# caliper.net
KiCad netlist of a schematic drawn in EAGLE
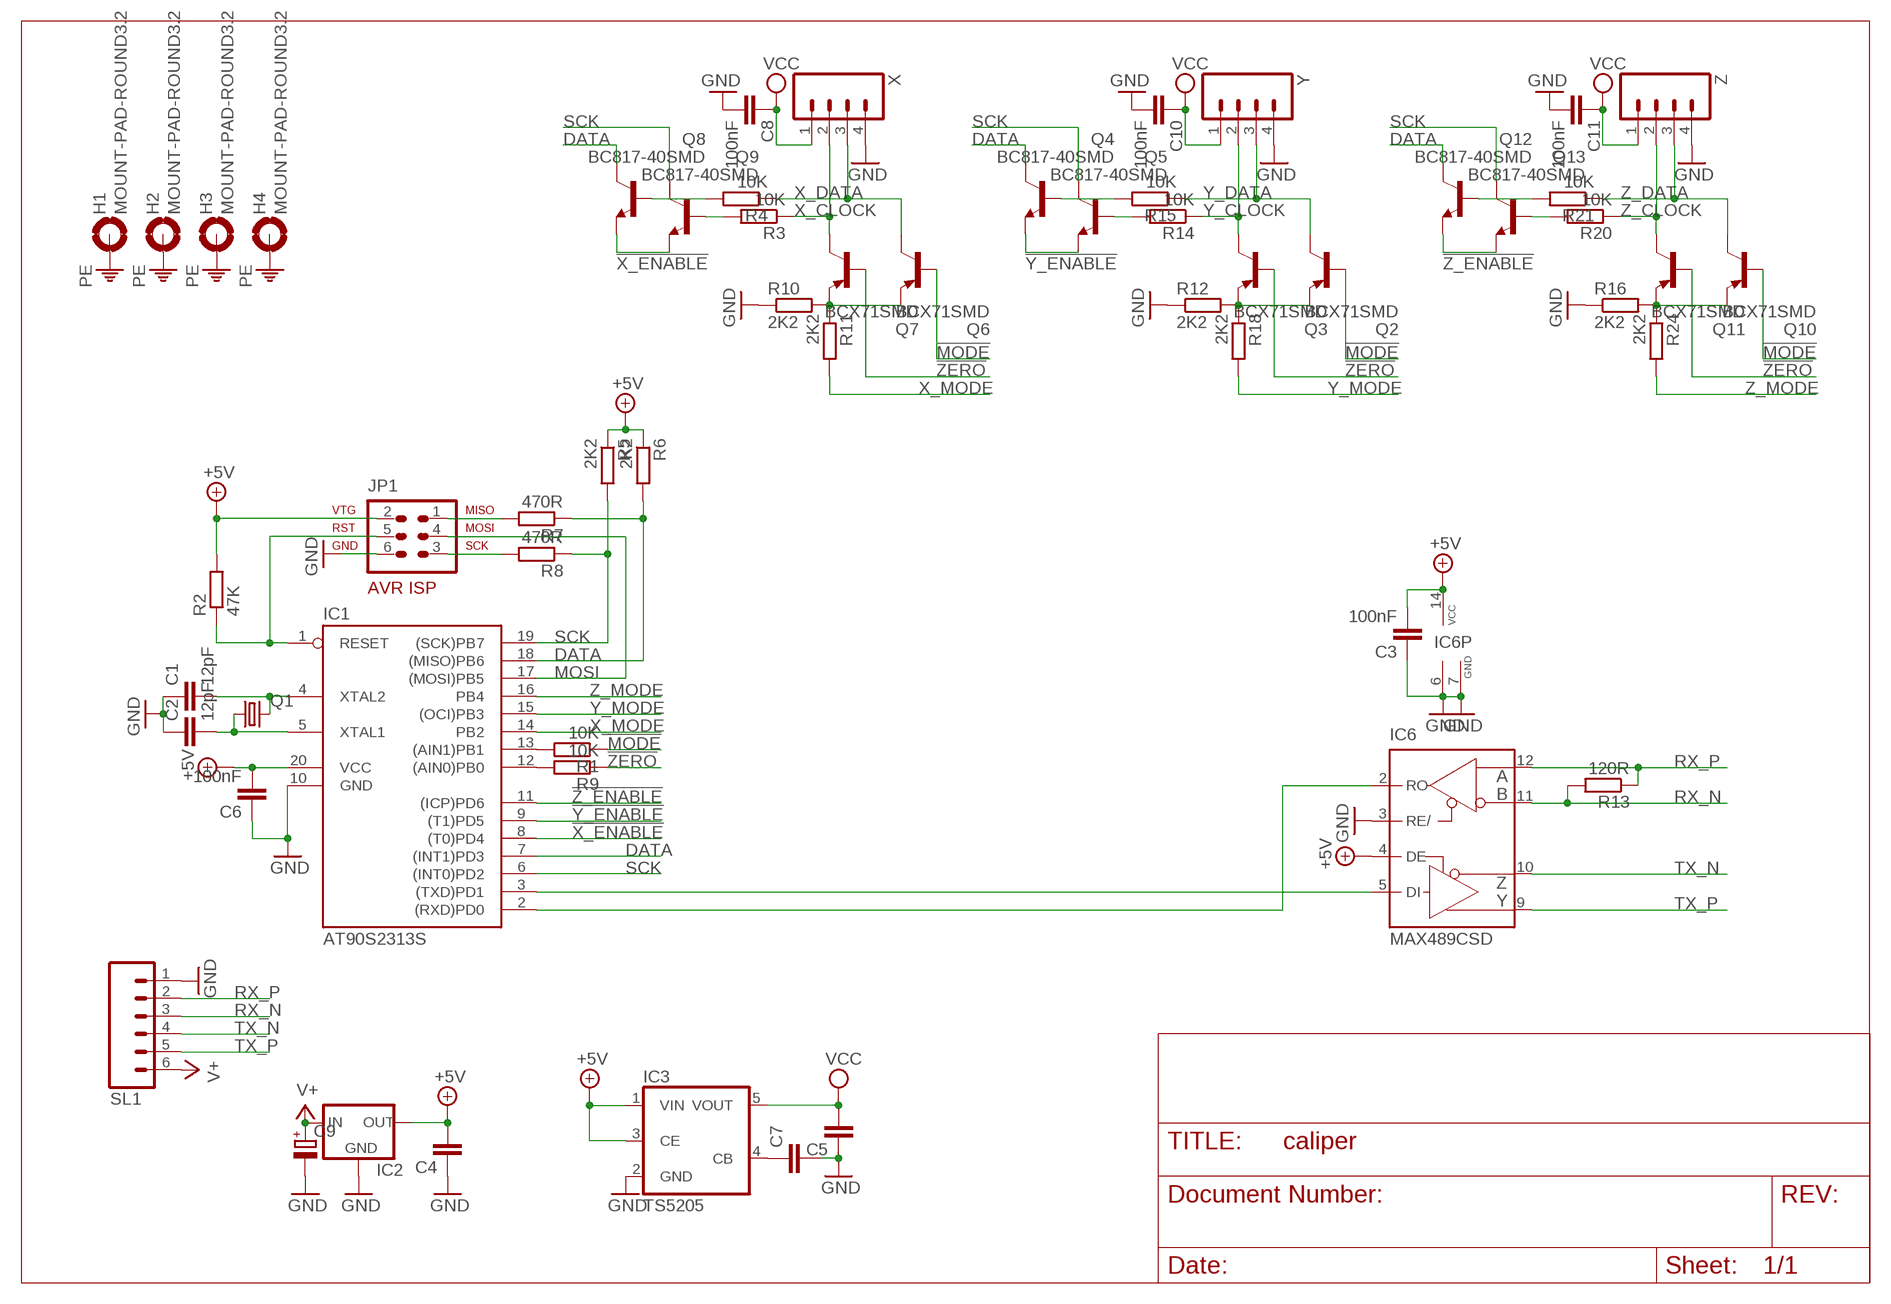
[diagram p0: schematic, sheet 1]

(export (version "E")
  (design (tool "Eeschema 10.0.6"))
  (components
    (comp (ref "C1")
      (value "12pF")
      (footprint "eagle-import:C0805")
      (libsource (lib "eagle-import") (part "C-EUC0805"))
    )
    (comp (ref "C2")
      (value "12pF")
      (footprint "eagle-import:C0805")
      (libsource (lib "eagle-import") (part "C-EUC0805"))
    )
    (comp (ref "C3")
      (value "100nF")
      (footprint "eagle-import:C0805")
      (libsource (lib "eagle-import") (part "C-EUC0805"))
    )
    (comp (ref "C4")
      (value "C-EUC0805")
      (footprint "eagle-import:C0805")
      (libsource (lib "eagle-import") (part "C-EUC0805"))
    )
    (comp (ref "C5")
      (value "C-EUC0805")
      (footprint "eagle-import:C0805")
      (libsource (lib "eagle-import") (part "C-EUC0805"))
    )
    (comp (ref "C6")
      (value "100nF")
      (footprint "eagle-import:C0805")
      (libsource (lib "eagle-import") (part "C-EUC0805"))
    )
    (comp (ref "C7")
      (value "C-EUC0805")
      (footprint "eagle-import:C0805")
      (libsource (lib "eagle-import") (part "C-EUC0805"))
    )
    (comp (ref "C8")
      (value "100nF")
      (footprint "eagle-import:C0805")
      (libsource (lib "eagle-import") (part "C-EUC0805"))
    )
    (comp (ref "C9")
      (value "CPOL-EUE3.5-8")
      (footprint "eagle-import:E3,5-8")
      (libsource (lib "eagle-import") (part "CPOL-EUE3.5-8"))
    )
    (comp (ref "C10")
      (value "100nF")
      (footprint "eagle-import:C0805")
      (libsource (lib "eagle-import") (part "C-EUC0805"))
    )
    (comp (ref "C11")
      (value "100nF")
      (footprint "eagle-import:C0805")
      (libsource (lib "eagle-import") (part "C-EUC0805"))
    )
    (comp (ref "H1")
      (value "MOUNT-PAD-ROUND3.2")
      (footprint "eagle-import:3,2-PAD")
      (libsource (lib "eagle-import") (part "MOUNT-PAD-ROUND3.2"))
    )
    (comp (ref "H2")
      (value "MOUNT-PAD-ROUND3.2")
      (footprint "eagle-import:3,2-PAD")
      (libsource (lib "eagle-import") (part "MOUNT-PAD-ROUND3.2"))
    )
    (comp (ref "H3")
      (value "MOUNT-PAD-ROUND3.2")
      (footprint "eagle-import:3,2-PAD")
      (libsource (lib "eagle-import") (part "MOUNT-PAD-ROUND3.2"))
    )
    (comp (ref "H4")
      (value "MOUNT-PAD-ROUND3.2")
      (footprint "eagle-import:3,2-PAD")
      (libsource (lib "eagle-import") (part "MOUNT-PAD-ROUND3.2"))
    )
    (comp (ref "IC1")
      (value "AT90S2313S")
      (footprint "eagle-import:SO20L")
      (libsource (lib "eagle-import") (part "AT90S2313S"))
    )
    (comp (ref "IC2")
      (value "78XXS")
      (footprint "eagle-import:78XXS")
      (libsource (lib "eagle-import") (part "78XXS"))
    )
    (comp (ref "IC3")
      (value "TS5205")
      (footprint "eagle-import:SOT25")
      (libsource (lib "eagle-import") (part "TS5205"))
    )
    (comp (ref "IC6")
      (value "MAX489CSD")
      (footprint "eagle-import:SO14")
      (libsource (lib "eagle-import") (part "MAX489CSD"))
    )
    (comp (ref "JP1")
      (value "AVR-ISP-6")
      (footprint "eagle-import:AVR-ISP-6")
      (libsource (lib "eagle-import") (part "AVR-ISP-6"))
    )
    (comp (ref "Q1")
      (value "CRYTALHC49S")
      (footprint "eagle-import:HC49_S")
      (libsource (lib "eagle-import") (part "CRYTALHC49S"))
    )
    (comp (ref "Q2")
      (value "BCX71SMD")
      (footprint "eagle-import:SOT23")
      (libsource (lib "eagle-import") (part "BCX71SMD"))
    )
    (comp (ref "Q3")
      (value "BCX71SMD")
      (footprint "eagle-import:SOT23")
      (libsource (lib "eagle-import") (part "BCX71SMD"))
    )
    (comp (ref "Q4")
      (value "BC817-40SMD")
      (footprint "eagle-import:SOT23-BEC")
      (libsource (lib "eagle-import") (part "BC817SMD-40"))
    )
    (comp (ref "Q5")
      (value "BC817-40SMD")
      (footprint "eagle-import:SOT23-BEC")
      (libsource (lib "eagle-import") (part "BC817SMD-40"))
    )
    (comp (ref "Q6")
      (value "BCX71SMD")
      (footprint "eagle-import:SOT23")
      (libsource (lib "eagle-import") (part "BCX71SMD"))
    )
    (comp (ref "Q7")
      (value "BCX71SMD")
      (footprint "eagle-import:SOT23")
      (libsource (lib "eagle-import") (part "BCX71SMD"))
    )
    (comp (ref "Q8")
      (value "BC817-40SMD")
      (footprint "eagle-import:SOT23-BEC")
      (libsource (lib "eagle-import") (part "BC817SMD-40"))
    )
    (comp (ref "Q9")
      (value "BC817-40SMD")
      (footprint "eagle-import:SOT23-BEC")
      (libsource (lib "eagle-import") (part "BC817SMD-40"))
    )
    (comp (ref "Q10")
      (value "BCX71SMD")
      (footprint "eagle-import:SOT23")
      (libsource (lib "eagle-import") (part "BCX71SMD"))
    )
    (comp (ref "Q11")
      (value "BCX71SMD")
      (footprint "eagle-import:SOT23")
      (libsource (lib "eagle-import") (part "BCX71SMD"))
    )
    (comp (ref "Q12")
      (value "BC817-40SMD")
      (footprint "eagle-import:SOT23-BEC")
      (libsource (lib "eagle-import") (part "BC817SMD-40"))
    )
    (comp (ref "Q13")
      (value "BC817-40SMD")
      (footprint "eagle-import:SOT23-BEC")
      (libsource (lib "eagle-import") (part "BC817SMD-40"))
    )
    (comp (ref "R1")
      (value "10K")
      (footprint "eagle-import:R0805")
      (libsource (lib "eagle-import") (part "R-EU_R0805"))
    )
    (comp (ref "R2")
      (value "47K")
      (footprint "eagle-import:R0805")
      (libsource (lib "eagle-import") (part "R-EU_R0805"))
    )
    (comp (ref "R3")
      (value "10K")
      (footprint "eagle-import:R0805")
      (libsource (lib "eagle-import") (part "R-EU_R0805"))
    )
    (comp (ref "R4")
      (value "10K")
      (footprint "eagle-import:R0805")
      (libsource (lib "eagle-import") (part "R-EU_R0805"))
    )
    (comp (ref "R5")
      (value "2K2")
      (footprint "eagle-import:R0805")
      (libsource (lib "eagle-import") (part "R-EU_R0805"))
    )
    (comp (ref "R6")
      (value "2K2")
      (footprint "eagle-import:R0805")
      (libsource (lib "eagle-import") (part "R-EU_R0805"))
    )
    (comp (ref "R7")
      (value "470R")
      (footprint "eagle-import:R0805")
      (libsource (lib "eagle-import") (part "R-EU_R0805"))
    )
    (comp (ref "R8")
      (value "470R")
      (footprint "eagle-import:R0805")
      (libsource (lib "eagle-import") (part "R-EU_R0805"))
    )
    (comp (ref "R9")
      (value "10K")
      (footprint "eagle-import:R0805")
      (libsource (lib "eagle-import") (part "R-EU_R0805"))
    )
    (comp (ref "R10")
      (value "2K2")
      (footprint "eagle-import:R0805")
      (libsource (lib "eagle-import") (part "R-EU_R0805"))
    )
    (comp (ref "R11")
      (value "2K2")
      (footprint "eagle-import:R0805")
      (libsource (lib "eagle-import") (part "R-EU_R0805"))
    )
    (comp (ref "R12")
      (value "2K2")
      (footprint "eagle-import:R0805")
      (libsource (lib "eagle-import") (part "R-EU_R0805"))
    )
    (comp (ref "R13")
      (value "120R")
      (footprint "eagle-import:R0805")
      (libsource (lib "eagle-import") (part "R-EU_R0805"))
    )
    (comp (ref "R14")
      (value "10K")
      (footprint "eagle-import:R0805")
      (libsource (lib "eagle-import") (part "R-EU_R0805"))
    )
    (comp (ref "R15")
      (value "10K")
      (footprint "eagle-import:R0805")
      (libsource (lib "eagle-import") (part "R-EU_R0805"))
    )
    (comp (ref "R16")
      (value "2K2")
      (footprint "eagle-import:R0805")
      (libsource (lib "eagle-import") (part "R-EU_R0805"))
    )
    (comp (ref "R18")
      (value "2K2")
      (footprint "eagle-import:R0805")
      (libsource (lib "eagle-import") (part "R-EU_R0805"))
    )
    (comp (ref "R20")
      (value "10K")
      (footprint "eagle-import:R0805")
      (libsource (lib "eagle-import") (part "R-EU_R0805"))
    )
    (comp (ref "R21")
      (value "10K")
      (footprint "eagle-import:R0805")
      (libsource (lib "eagle-import") (part "R-EU_R0805"))
    )
    (comp (ref "R24")
      (value "2K2")
      (footprint "eagle-import:R0805")
      (libsource (lib "eagle-import") (part "R-EU_R0805"))
    )
    (comp (ref "SL1")
      (value "M06")
      (footprint "eagle-import:06P")
      (libsource (lib "eagle-import") (part "M06"))
    )
    (comp (ref "X")
      (value "M04")
      (footprint "eagle-import:04P")
      (libsource (lib "eagle-import") (part "M04"))
    )
    (comp (ref "Y")
      (value "M04")
      (footprint "eagle-import:04P")
      (libsource (lib "eagle-import") (part "M04"))
    )
    (comp (ref "Z")
      (value "M04")
      (footprint "eagle-import:04P")
      (libsource (lib "eagle-import") (part "M04"))
    )
  )
  (nets
    (net (code "1") (name "+5V") (class "Default")
      (node (ref "C3") (pin "2") (pinfunction "2_2") (pintype "passive"))
      (node (ref "C4") (pin "2") (pinfunction "2_2") (pintype "passive"))
      (node (ref "C6") (pin "2") (pinfunction "2_2") (pintype "passive"))
      (node (ref "IC1") (pin "20") (pinfunction "VCC_20") (pintype "power_in"))
      (node (ref "IC2") (pin "OUT") (pinfunction "OUT_OUT") (pintype "passive"))
      (node (ref "IC3") (pin "1") (pinfunction "VIN_1") (pintype "input"))
      (node (ref "IC3") (pin "3") (pinfunction "CE_3") (pintype "input"))
      (node (ref "IC6") (pin "14") (pinfunction "VCC_14") (pintype "power_in"))
      (node (ref "IC6") (pin "4") (pinfunction "DE_4") (pintype "input"))
      (node (ref "JP1") (pin "2") (pinfunction "2_2") (pintype "passive"))
      (node (ref "R2") (pin "2") (pinfunction "2_2") (pintype "passive"))
      (node (ref "R5") (pin "1") (pinfunction "1_1") (pintype "passive"))
      (node (ref "R6") (pin "1") (pinfunction "1_1") (pintype "passive"))
    )
    (net (code "2") (name "/DATA") (class "Default")
      (node (ref "IC1") (pin "18") (pinfunction "(MISO)PB6_18") (pintype "bidirectional"))
      (node (ref "IC1") (pin "7") (pinfunction "(INT1)PD3_7") (pintype "bidirectional"))
      (node (ref "Q12") (pin "C") (pinfunction "C_C") (pintype "passive"))
      (node (ref "Q4") (pin "C") (pinfunction "C_C") (pintype "passive"))
      (node (ref "Q8") (pin "C") (pinfunction "C_C") (pintype "passive"))
      (node (ref "R6") (pin "2") (pinfunction "2_2") (pintype "passive"))
      (node (ref "R7") (pin "1") (pinfunction "1_1") (pintype "passive"))
    )
    (net (code "3") (name "/MOSI") (class "Default")
      (node (ref "IC1") (pin "17") (pinfunction "(MOSI)PB5_17") (pintype "bidirectional"))
      (node (ref "JP1") (pin "4") (pinfunction "4_4") (pintype "passive"))
    )
    (net (code "4") (name "/RX_N") (class "Default")
      (node (ref "IC6") (pin "11") (pinfunction "B_11") (pintype "passive"))
      (node (ref "R13") (pin "2") (pinfunction "2_2") (pintype "passive"))
      (node (ref "SL1") (pin "3") (pinfunction "3_3") (pintype "passive"))
    )
    (net (code "5") (name "/RX_P") (class "Default")
      (node (ref "IC6") (pin "12") (pinfunction "A_12") (pintype "passive"))
      (node (ref "R13") (pin "1") (pinfunction "1_1") (pintype "passive"))
      (node (ref "SL1") (pin "2") (pinfunction "2_2") (pintype "passive"))
    )
    (net (code "6") (name "/SCK") (class "Default")
      (node (ref "IC1") (pin "19") (pinfunction "(SCK)PB7_19") (pintype "bidirectional"))
      (node (ref "IC1") (pin "6") (pinfunction "(INT0)PD2_6") (pintype "bidirectional"))
      (node (ref "Q13") (pin "C") (pinfunction "C_C") (pintype "passive"))
      (node (ref "Q5") (pin "C") (pinfunction "C_C") (pintype "passive"))
      (node (ref "Q9") (pin "C") (pinfunction "C_C") (pintype "passive"))
      (node (ref "R5") (pin "2") (pinfunction "2_2") (pintype "passive"))
      (node (ref "R8") (pin "1") (pinfunction "1_1") (pintype "passive"))
    )
    (net (code "7") (name "/TX_N") (class "Default")
      (node (ref "IC6") (pin "10") (pinfunction "Z_10") (pintype "passive"))
      (node (ref "SL1") (pin "4") (pinfunction "4_4") (pintype "passive"))
    )
    (net (code "8") (name "/TX_P") (class "Default")
      (node (ref "IC6") (pin "9") (pinfunction "Y_9") (pintype "passive"))
      (node (ref "SL1") (pin "5") (pinfunction "5_5") (pintype "passive"))
    )
    (net (code "9") (name "/X_CLOCK") (class "Default")
      (node (ref "Q7") (pin "3") (pinfunction "C_3") (pintype "passive"))
      (node (ref "R3") (pin "1") (pinfunction "1_1") (pintype "passive"))
      (node (ref "X") (pin "2") (pinfunction "2_2") (pintype "passive"))
    )
    (net (code "10") (name "/X_DATA") (class "Default")
      (node (ref "Q6") (pin "3") (pinfunction "C_3") (pintype "passive"))
      (node (ref "R4") (pin "1") (pinfunction "1_1") (pintype "passive"))
      (node (ref "X") (pin "3") (pinfunction "3_3") (pintype "passive"))
    )
    (net (code "11") (name "/X_MODE") (class "Default")
      (node (ref "IC1") (pin "14") (pinfunction "PB2_14") (pintype "bidirectional"))
      (node (ref "R11") (pin "2") (pinfunction "2_2") (pintype "passive"))
    )
    (net (code "12") (name "/Y_CLOCK") (class "Default")
      (node (ref "Q3") (pin "3") (pinfunction "C_3") (pintype "passive"))
      (node (ref "R14") (pin "1") (pinfunction "1_1") (pintype "passive"))
      (node (ref "Y") (pin "2") (pinfunction "2_2") (pintype "passive"))
    )
    (net (code "13") (name "/Y_DATA") (class "Default")
      (node (ref "Q2") (pin "3") (pinfunction "C_3") (pintype "passive"))
      (node (ref "R15") (pin "1") (pinfunction "1_1") (pintype "passive"))
      (node (ref "Y") (pin "3") (pinfunction "3_3") (pintype "passive"))
    )
    (net (code "14") (name "/Y_MODE") (class "Default")
      (node (ref "IC1") (pin "15") (pinfunction "(OCI)PB3_15") (pintype "bidirectional"))
      (node (ref "R18") (pin "2") (pinfunction "2_2") (pintype "passive"))
    )
    (net (code "15") (name "/Z_CLOCK") (class "Default")
      (node (ref "Q11") (pin "3") (pinfunction "C_3") (pintype "passive"))
      (node (ref "R20") (pin "1") (pinfunction "1_1") (pintype "passive"))
      (node (ref "Z") (pin "2") (pinfunction "2_2") (pintype "passive"))
    )
    (net (code "16") (name "/Z_DATA") (class "Default")
      (node (ref "Q10") (pin "3") (pinfunction "C_3") (pintype "passive"))
      (node (ref "R21") (pin "1") (pinfunction "1_1") (pintype "passive"))
      (node (ref "Z") (pin "3") (pinfunction "3_3") (pintype "passive"))
    )
    (net (code "17") (name "/Z_MODE") (class "Default")
      (node (ref "IC1") (pin "16") (pinfunction "PB4_16") (pintype "bidirectional"))
      (node (ref "R24") (pin "2") (pinfunction "2_2") (pintype "passive"))
    )
    (net (code "18") (name "/~{MODE}") (class "Default")
      (node (ref "Q10") (pin "1") (pinfunction "B_1") (pintype "passive"))
      (node (ref "Q2") (pin "1") (pinfunction "B_1") (pintype "passive"))
      (node (ref "Q6") (pin "1") (pinfunction "B_1") (pintype "passive"))
      (node (ref "R1") (pin "1") (pinfunction "1_1") (pintype "passive"))
    )
    (net (code "19") (name "/~{X_ENABLE}") (class "Default")
      (node (ref "IC1") (pin "8") (pinfunction "(T0)PD4_8") (pintype "bidirectional"))
      (node (ref "Q8") (pin "E") (pinfunction "E_E") (pintype "passive"))
      (node (ref "Q9") (pin "E") (pinfunction "E_E") (pintype "passive"))
    )
    (net (code "20") (name "/~{Y_ENABLE}") (class "Default")
      (node (ref "IC1") (pin "9") (pinfunction "(T1)PD5_9") (pintype "bidirectional"))
      (node (ref "Q4") (pin "E") (pinfunction "E_E") (pintype "passive"))
      (node (ref "Q5") (pin "E") (pinfunction "E_E") (pintype "passive"))
    )
    (net (code "21") (name "/~{ZERO}") (class "Default")
      (node (ref "Q11") (pin "1") (pinfunction "B_1") (pintype "passive"))
      (node (ref "Q3") (pin "1") (pinfunction "B_1") (pintype "passive"))
      (node (ref "Q7") (pin "1") (pinfunction "B_1") (pintype "passive"))
      (node (ref "R9") (pin "1") (pinfunction "1_1") (pintype "passive"))
    )
    (net (code "22") (name "/~{Z_ENABLE}") (class "Default")
      (node (ref "IC1") (pin "11") (pinfunction "(ICP)PD6_11") (pintype "bidirectional"))
      (node (ref "Q12") (pin "E") (pinfunction "E_E") (pintype "passive"))
      (node (ref "Q13") (pin "E") (pinfunction "E_E") (pintype "passive"))
    )
    (net (code "23") (name "GND") (class "Default")
      (node (ref "C1") (pin "1") (pinfunction "1_1") (pintype "passive"))
      (node (ref "C10") (pin "2") (pinfunction "2_2") (pintype "passive"))
      (node (ref "C11") (pin "2") (pinfunction "2_2") (pintype "passive"))
      (node (ref "C2") (pin "1") (pinfunction "1_1") (pintype "passive"))
      (node (ref "C3") (pin "1") (pinfunction "1_1") (pintype "passive"))
      (node (ref "C4") (pin "1") (pinfunction "1_1") (pintype "passive"))
      (node (ref "C5") (pin "1") (pinfunction "1_1") (pintype "passive"))
      (node (ref "C6") (pin "1") (pinfunction "1_1") (pintype "passive"))
      (node (ref "C7") (pin "2") (pinfunction "2_2") (pintype "passive"))
      (node (ref "C8") (pin "2") (pinfunction "2_2") (pintype "passive"))
      (node (ref "C9") (pin "-") (pinfunction "-_-") (pintype "passive"))
      (node (ref "IC1") (pin "10") (pinfunction "GND_10") (pintype "power_in"))
      (node (ref "IC2") (pin "GND") (pinfunction "GND_GND") (pintype "input"))
      (node (ref "IC3") (pin "2") (pinfunction "GND_2") (pintype "passive"))
      (node (ref "IC6") (pin "3") (pinfunction "RE/_3") (pintype "input"))
      (node (ref "IC6") (pin "6") (pinfunction "GND_6") (pintype "power_in"))
      (node (ref "IC6") (pin "7") (pinfunction "GND_7") (pintype "power_in"))
      (node (ref "JP1") (pin "6") (pinfunction "6_6") (pintype "passive"))
      (node (ref "R10") (pin "1") (pinfunction "1_1") (pintype "passive"))
      (node (ref "R12") (pin "1") (pinfunction "1_1") (pintype "passive"))
      (node (ref "R16") (pin "1") (pinfunction "1_1") (pintype "passive"))
      (node (ref "SL1") (pin "1") (pinfunction "1_1") (pintype "passive"))
      (node (ref "X") (pin "4") (pinfunction "4_4") (pintype "passive"))
      (node (ref "Y") (pin "4") (pinfunction "4_4") (pintype "passive"))
      (node (ref "Z") (pin "4") (pinfunction "4_4") (pintype "passive"))
    )
    (net (code "24") (name "Net-(IC1-(AIN0)PB0)") (class "Default")
      (node (ref "IC1") (pin "12") (pinfunction "(AIN0)PB0_12") (pintype "bidirectional"))
      (node (ref "R9") (pin "2") (pinfunction "2_2") (pintype "passive"))
    )
    (net (code "25") (name "Net-(IC1-(AIN1)PB1)") (class "Default")
      (node (ref "IC1") (pin "13") (pinfunction "(AIN1)PB1_13") (pintype "bidirectional"))
      (node (ref "R1") (pin "2") (pinfunction "2_2") (pintype "passive"))
    )
    (net (code "26") (name "Net-(IC1-(RXD)PD0)") (class "Default")
      (node (ref "IC1") (pin "2") (pinfunction "(RXD)PD0_2") (pintype "bidirectional"))
      (node (ref "IC6") (pin "2") (pinfunction "RO_2") (pintype "output"))
    )
    (net (code "27") (name "Net-(IC1-(TXD)PD1)") (class "Default")
      (node (ref "IC1") (pin "3") (pinfunction "(TXD)PD1_3") (pintype "bidirectional"))
      (node (ref "IC6") (pin "5") (pinfunction "DI_5") (pintype "input"))
    )
    (net (code "28") (name "Net-(IC1-RESET)") (class "Default")
      (node (ref "IC1") (pin "1") (pinfunction "RESET_1") (pintype "bidirectional"))
      (node (ref "JP1") (pin "5") (pinfunction "5_5") (pintype "passive"))
      (node (ref "R2") (pin "1") (pinfunction "1_1") (pintype "passive"))
    )
    (net (code "29") (name "Net-(IC1-XTAL1)") (class "Default")
      (node (ref "C2") (pin "2") (pinfunction "2_2") (pintype "passive"))
      (node (ref "IC1") (pin "5") (pinfunction "XTAL1_5") (pintype "bidirectional"))
      (node (ref "Q1") (pin "1") (pinfunction "1_1") (pintype "passive"))
    )
    (net (code "30") (name "Net-(IC1-XTAL2)") (class "Default")
      (node (ref "C1") (pin "2") (pinfunction "2_2") (pintype "passive"))
      (node (ref "IC1") (pin "4") (pinfunction "XTAL2_4") (pintype "bidirectional"))
      (node (ref "Q1") (pin "2") (pinfunction "2_2") (pintype "passive"))
    )
    (net (code "31") (name "Net-(IC3-CB)") (class "Default")
      (node (ref "C7") (pin "1") (pinfunction "1_1") (pintype "passive"))
      (node (ref "IC3") (pin "4") (pinfunction "CB_4") (pintype "input"))
    )
    (net (code "32") (name "Net-(JP1-Pad1)") (class "Default")
      (node (ref "JP1") (pin "1") (pinfunction "1_1") (pintype "passive"))
      (node (ref "R7") (pin "2") (pinfunction "2_2") (pintype "passive"))
    )
    (net (code "33") (name "Net-(JP1-Pad3)") (class "Default")
      (node (ref "JP1") (pin "3") (pinfunction "3_3") (pintype "passive"))
      (node (ref "R8") (pin "2") (pinfunction "2_2") (pintype "passive"))
    )
    (net (code "34") (name "Net-(Q2-E)") (class "Default")
      (node (ref "Q2") (pin "2") (pinfunction "E_2") (pintype "passive"))
      (node (ref "Q3") (pin "2") (pinfunction "E_2") (pintype "passive"))
      (node (ref "R12") (pin "2") (pinfunction "2_2") (pintype "passive"))
      (node (ref "R18") (pin "1") (pinfunction "1_1") (pintype "passive"))
    )
    (net (code "35") (name "Net-(Q4-PadB)") (class "Default")
      (node (ref "Q4") (pin "B") (pinfunction "B_B") (pintype "passive"))
      (node (ref "R15") (pin "2") (pinfunction "2_2") (pintype "passive"))
    )
    (net (code "36") (name "Net-(Q5-PadB)") (class "Default")
      (node (ref "Q5") (pin "B") (pinfunction "B_B") (pintype "passive"))
      (node (ref "R14") (pin "2") (pinfunction "2_2") (pintype "passive"))
    )
    (net (code "37") (name "Net-(Q6-E)") (class "Default")
      (node (ref "Q6") (pin "2") (pinfunction "E_2") (pintype "passive"))
      (node (ref "Q7") (pin "2") (pinfunction "E_2") (pintype "passive"))
      (node (ref "R10") (pin "2") (pinfunction "2_2") (pintype "passive"))
      (node (ref "R11") (pin "1") (pinfunction "1_1") (pintype "passive"))
    )
    (net (code "38") (name "Net-(Q8-PadB)") (class "Default")
      (node (ref "Q8") (pin "B") (pinfunction "B_B") (pintype "passive"))
      (node (ref "R4") (pin "2") (pinfunction "2_2") (pintype "passive"))
    )
    (net (code "39") (name "Net-(Q9-PadB)") (class "Default")
      (node (ref "Q9") (pin "B") (pinfunction "B_B") (pintype "passive"))
      (node (ref "R3") (pin "2") (pinfunction "2_2") (pintype "passive"))
    )
    (net (code "40") (name "Net-(Q10-E)") (class "Default")
      (node (ref "Q10") (pin "2") (pinfunction "E_2") (pintype "passive"))
      (node (ref "Q11") (pin "2") (pinfunction "E_2") (pintype "passive"))
      (node (ref "R16") (pin "2") (pinfunction "2_2") (pintype "passive"))
      (node (ref "R24") (pin "1") (pinfunction "1_1") (pintype "passive"))
    )
    (net (code "41") (name "Net-(Q12-PadB)") (class "Default")
      (node (ref "Q12") (pin "B") (pinfunction "B_B") (pintype "passive"))
      (node (ref "R21") (pin "2") (pinfunction "2_2") (pintype "passive"))
    )
    (net (code "42") (name "Net-(Q13-PadB)") (class "Default")
      (node (ref "Q13") (pin "B") (pinfunction "B_B") (pintype "passive"))
      (node (ref "R20") (pin "2") (pinfunction "2_2") (pintype "passive"))
    )
    (net (code "43") (name "PE") (class "Default")
      (node (ref "H1") (pin "B3,2") (pinfunction "MOUNT_B3,2") (pintype "passive"))
      (node (ref "H2") (pin "B3,2") (pinfunction "MOUNT_B3,2") (pintype "passive"))
      (node (ref "H3") (pin "B3,2") (pinfunction "MOUNT_B3,2") (pintype "passive"))
      (node (ref "H4") (pin "B3,2") (pinfunction "MOUNT_B3,2") (pintype "passive"))
    )
    (net (code "44") (name "V+") (class "Default")
      (node (ref "C9") (pin "+") (pinfunction "+_+") (pintype "passive"))
      (node (ref "IC2") (pin "IN") (pinfunction "IN_IN") (pintype "input"))
      (node (ref "SL1") (pin "6") (pinfunction "6_6") (pintype "passive"))
    )
    (net (code "45") (name "VCC") (class "Default")
      (node (ref "C10") (pin "1") (pinfunction "1_1") (pintype "passive"))
      (node (ref "C11") (pin "1") (pinfunction "1_1") (pintype "passive"))
      (node (ref "C5") (pin "2") (pinfunction "2_2") (pintype "passive"))
      (node (ref "C8") (pin "1") (pinfunction "1_1") (pintype "passive"))
      (node (ref "IC3") (pin "5") (pinfunction "VOUT_5") (pintype "passive"))
      (node (ref "X") (pin "1") (pinfunction "1_1") (pintype "passive"))
      (node (ref "Y") (pin "1") (pinfunction "1_1") (pintype "passive"))
      (node (ref "Z") (pin "1") (pinfunction "1_1") (pintype "passive"))
    )
  )
)
